# boson.net
KiCad netlist of a schematic drawn in EAGLE
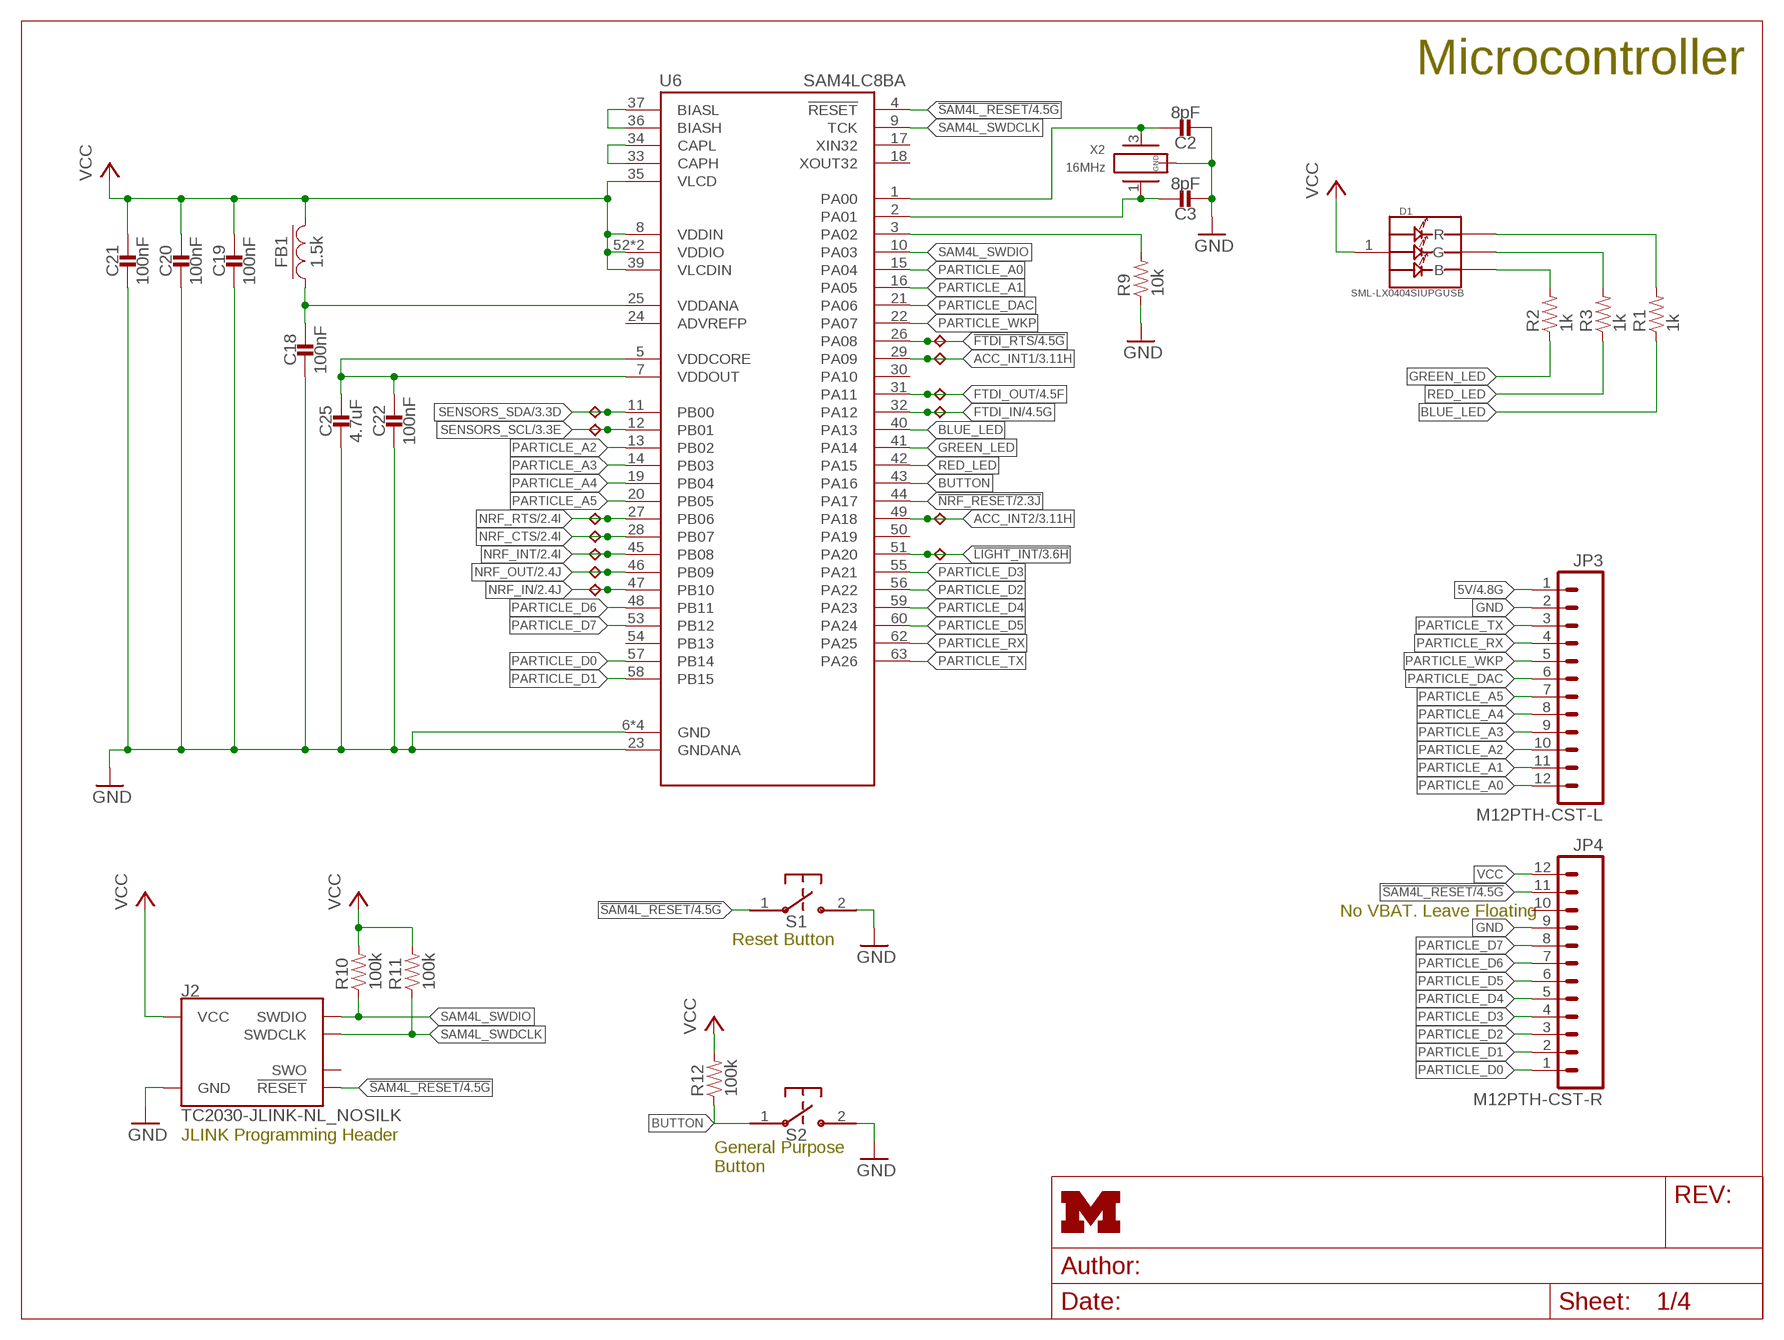
[diagram p0: schematic, sheet 1]
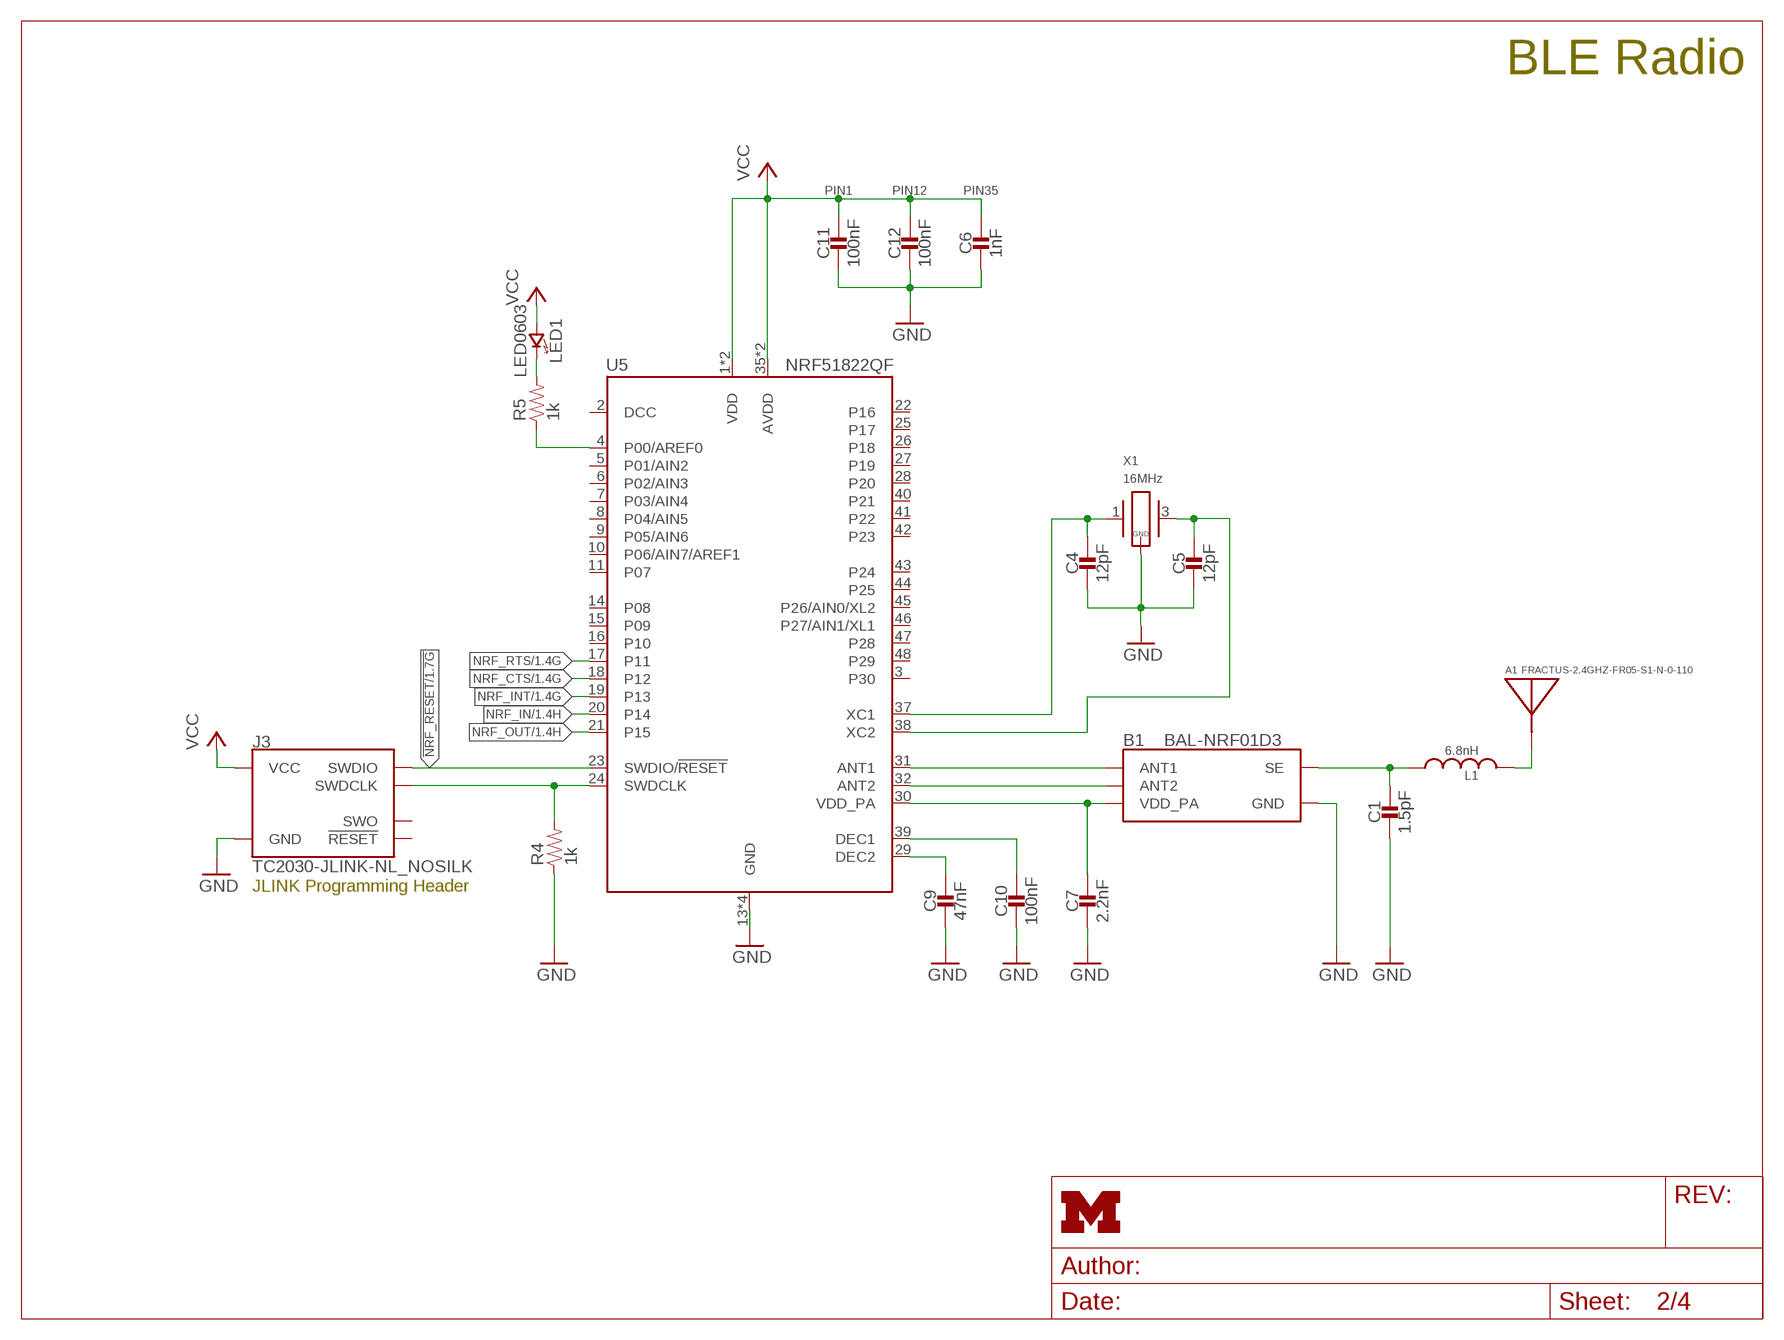
[diagram p1: schematic, sheet 2]
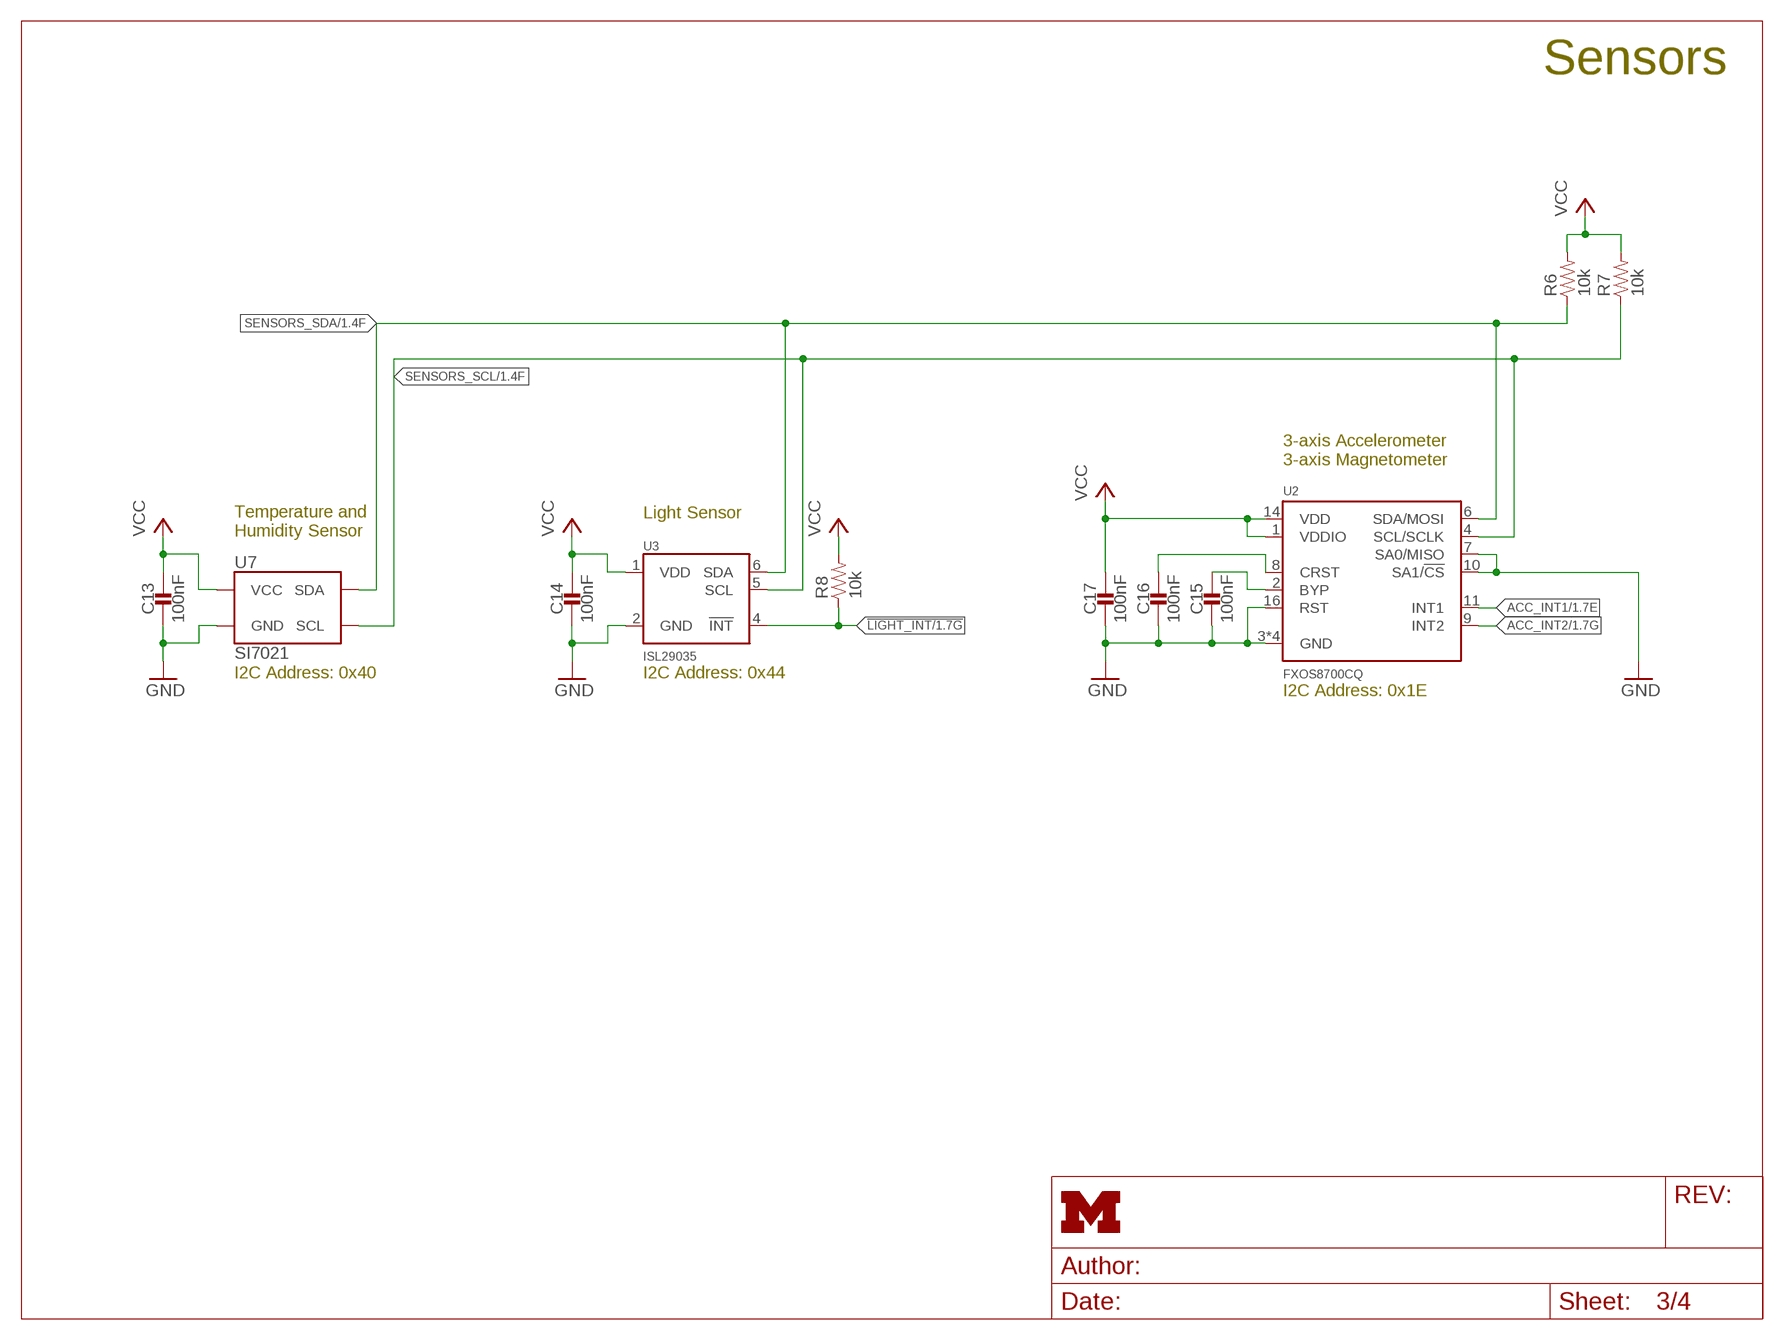
[diagram p2: schematic, sheet 3]
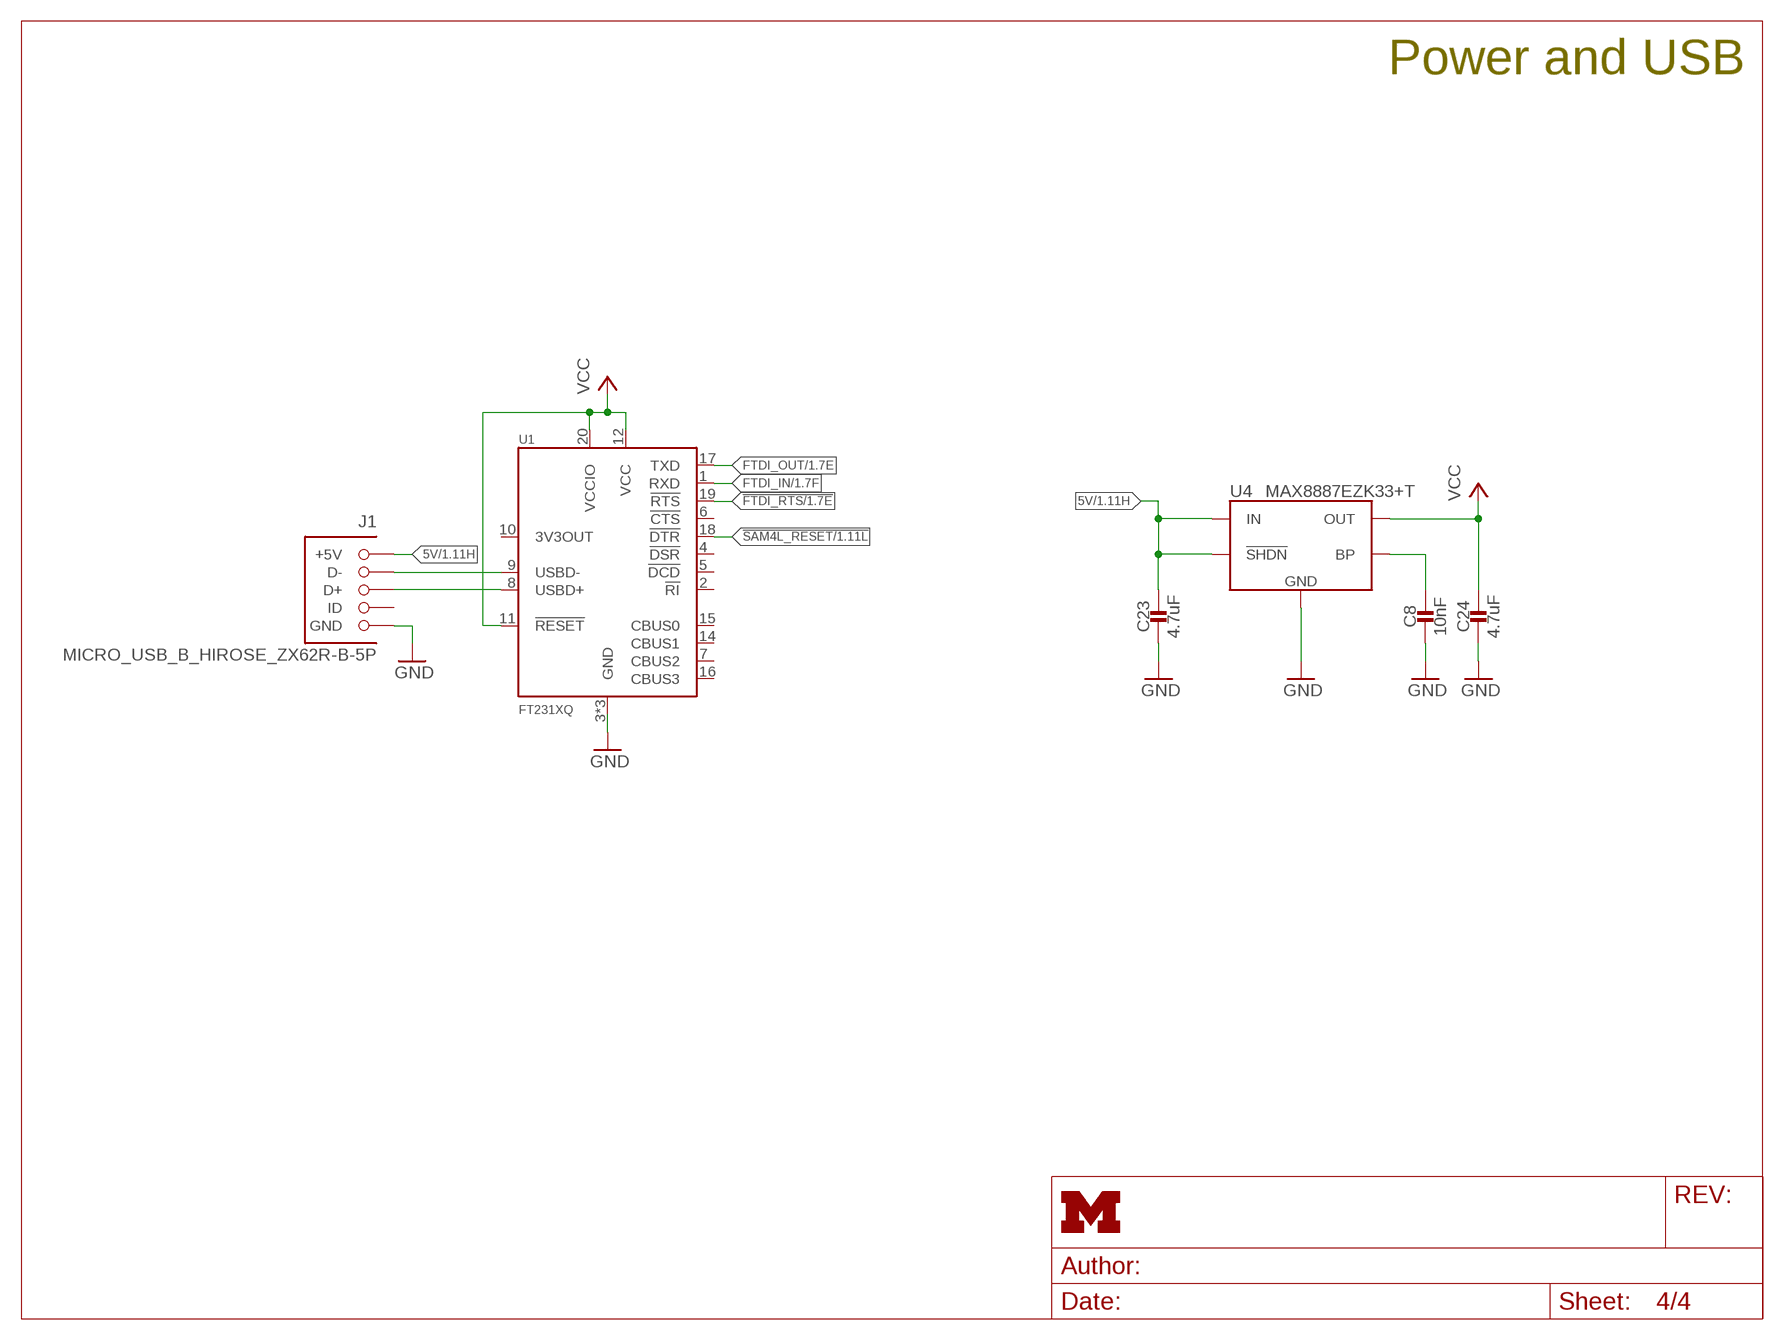
[diagram p3: schematic, sheet 4]

(export (version "E")
  (design (tool "Eeschema 10.0.6"))
  (components
    (comp (ref "C2")
      (value "8pF")
      (footprint "eagle-import:0402_CAP")
      (libsource (lib "eagle-import") (part "CAPACITOR0402_CAP"))
    )
    (comp (ref "C3")
      (value "8pF")
      (footprint "eagle-import:0402_CAP")
      (libsource (lib "eagle-import") (part "CAPACITOR0402_CAP"))
    )
    (comp (ref "C18")
      (value "100nF")
      (footprint "eagle-import:0402_CAP")
      (libsource (lib "eagle-import") (part "CAPACITOR0402_CAP"))
    )
    (comp (ref "C19")
      (value "100nF")
      (footprint "eagle-import:0402_CAP")
      (libsource (lib "eagle-import") (part "CAPACITOR0402_CAP"))
    )
    (comp (ref "C20")
      (value "100nF")
      (footprint "eagle-import:0402_CAP")
      (libsource (lib "eagle-import") (part "CAPACITOR0402_CAP"))
    )
    (comp (ref "C21")
      (value "100nF")
      (footprint "eagle-import:0402_CAP")
      (libsource (lib "eagle-import") (part "CAPACITOR0402_CAP"))
    )
    (comp (ref "C22")
      (value "100nF")
      (footprint "eagle-import:0402_CAP")
      (libsource (lib "eagle-import") (part "CAPACITOR0402_CAP"))
    )
    (comp (ref "C25")
      (value "4.7uF")
      (footprint "eagle-import:0402_CAP")
      (libsource (lib "eagle-import") (part "CAPACITOR0402_CAP"))
    )
    (comp (ref "D1")
      (value "SML-LX0404SIUPGUSB")
      (footprint "eagle-import:1MM_SQ_4PAD")
      (libsource (lib "eagle-import") (part "SML-LX0404SIUPGUSB"))
    )
    (comp (ref "FB1")
      (value "1.5k")
      (footprint "eagle-import:0402_CAP")
      (libsource (lib "eagle-import") (part "FERRITE_BEAD0402"))
    )
    (comp (ref "J2")
      (value "TC2030-JLINK-NL_NOSILK")
      (footprint "eagle-import:TC2030-IDC-NL_NOSILK")
      (libsource (lib "eagle-import") (part "TC2030-JLINK-NL_NOSILK"))
    )
    (comp (ref "JP3")
      (value "M12PTH-CST-L")
      (footprint "eagle-import:1X12-CASTELLATED")
      (libsource (lib "eagle-import") (part "M12PTH-CST-L"))
    )
    (comp (ref "JP4")
      (value "M12PTH-CST-R")
      (footprint "eagle-import:1X12-CASTELLATED")
      (libsource (lib "eagle-import") (part "M12PTH-CST-R"))
    )
    (comp (ref "R1")
      (value "1k")
      (footprint "eagle-import:0402_RES")
      (libsource (lib "eagle-import") (part "RESISTOR0402_RES"))
    )
    (comp (ref "R2")
      (value "1k")
      (footprint "eagle-import:0402_RES")
      (libsource (lib "eagle-import") (part "RESISTOR0402_RES"))
    )
    (comp (ref "R3")
      (value "1k")
      (footprint "eagle-import:0402_RES")
      (libsource (lib "eagle-import") (part "RESISTOR0402_RES"))
    )
    (comp (ref "R9")
      (value "10k")
      (footprint "eagle-import:0402_RES")
      (libsource (lib "eagle-import") (part "RESISTOR0402_RES"))
    )
    (comp (ref "R10")
      (value "100k")
      (footprint "eagle-import:0402_RES")
      (libsource (lib "eagle-import") (part "RESISTOR0402_RES"))
    )
    (comp (ref "R11")
      (value "100k")
      (footprint "eagle-import:0402_RES")
      (libsource (lib "eagle-import") (part "RESISTOR0402_RES"))
    )
    (comp (ref "R12")
      (value "100k")
      (footprint "eagle-import:0402_RES")
      (libsource (lib "eagle-import") (part "RESISTOR0402_RES"))
    )
    (comp (ref "S1")
      (value "B3U-1000P")
      (footprint "eagle-import:B3U-1000P")
      (libsource (lib "eagle-import") (part "B3U-1000P"))
    )
    (comp (ref "S2")
      (value "B3U-1000P")
      (footprint "eagle-import:B3U-1000P")
      (libsource (lib "eagle-import") (part "B3U-1000P"))
    )
    (comp (ref "TP1")
      (value "TPB1,27")
      (footprint "eagle-import:B1,27")
      (libsource (lib "eagle-import") (part "TPB1,27"))
    )
    (comp (ref "TP2")
      (value "TPB1,27")
      (footprint "eagle-import:B1,27")
      (libsource (lib "eagle-import") (part "TPB1,27"))
    )
    (comp (ref "TP3")
      (value "TPB1,27")
      (footprint "eagle-import:B1,27")
      (libsource (lib "eagle-import") (part "TPB1,27"))
    )
    (comp (ref "TP4")
      (value "TPB1,27")
      (footprint "eagle-import:B1,27")
      (libsource (lib "eagle-import") (part "TPB1,27"))
    )
    (comp (ref "TP5")
      (value "TPB1,27")
      (footprint "eagle-import:B1,27")
      (libsource (lib "eagle-import") (part "TPB1,27"))
    )
    (comp (ref "TP6")
      (value "TPB1,27")
      (footprint "eagle-import:B1,27")
      (libsource (lib "eagle-import") (part "TPB1,27"))
    )
    (comp (ref "TP7")
      (value "TPB1,27")
      (footprint "eagle-import:B1,27")
      (libsource (lib "eagle-import") (part "TPB1,27"))
    )
    (comp (ref "TP8")
      (value "TPB1,27")
      (footprint "eagle-import:B1,27")
      (libsource (lib "eagle-import") (part "TPB1,27"))
    )
    (comp (ref "TP9")
      (value "TPB1,27")
      (footprint "eagle-import:B1,27")
      (libsource (lib "eagle-import") (part "TPB1,27"))
    )
    (comp (ref "TP10")
      (value "TPB1,27")
      (footprint "eagle-import:B1,27")
      (libsource (lib "eagle-import") (part "TPB1,27"))
    )
    (comp (ref "TP11")
      (value "TPB1,27")
      (footprint "eagle-import:B1,27")
      (libsource (lib "eagle-import") (part "TPB1,27"))
    )
    (comp (ref "TP12")
      (value "TPB1,27")
      (footprint "eagle-import:B1,27")
      (libsource (lib "eagle-import") (part "TPB1,27"))
    )
    (comp (ref "TP13")
      (value "TPB1,27")
      (footprint "eagle-import:B1,27")
      (libsource (lib "eagle-import") (part "TPB1,27"))
    )
    (comp (ref "U6")
      (value "SAM4LC8BA")
      (footprint "eagle-import:QFN-64-9MM")
      (libsource (lib "eagle-import") (part "SAM4LC8BA"))
    )
    (comp (ref "X2")
      (value "16MHz")
      (footprint "eagle-import:FHXXX")
      (libsource (lib "eagle-import") (part "FH1600015"))
    )
    (comp (ref "C8")
      (value "10nF")
      (footprint "eagle-import:0402_CAP")
      (libsource (lib "eagle-import") (part "CAPACITOR0402_CAP"))
    )
    (comp (ref "C23")
      (value "4.7uF")
      (footprint "eagle-import:0402_CAP")
      (libsource (lib "eagle-import") (part "CAPACITOR0402_CAP"))
    )
    (comp (ref "C24")
      (value "4.7uF")
      (footprint "eagle-import:0402_CAP")
      (libsource (lib "eagle-import") (part "CAPACITOR0402_CAP"))
    )
    (comp (ref "J1")
      (value "MICRO_USB_B_HIROSE_ZX62R-B-5P")
      (footprint "eagle-import:USB_MICRO_B-HIROSE-ZX62R-B-5P")
      (fields (field (name "DIGIKEY") "H125274CT-ND"))
      (libsource (lib "eagle-import") (part "MICRO_USB_B_HIROSE_ZX62R-B-5P"))
    )
    (comp (ref "U1")
      (value "FT231XQ")
      (footprint "eagle-import:QFN-20-4MM")
      (fields (field (name "MPN") "FT231XQ-R"))
      (libsource (lib "eagle-import") (part "FT231XQ"))
    )
    (comp (ref "U4")
      (value "MAX8887EZK33+T")
      (footprint "eagle-import:SOT-23-5")
      (libsource (lib "eagle-import") (part "MAX8887EZK33+T"))
    )
    (comp (ref "C13")
      (value "100nF")
      (footprint "eagle-import:0402_CAP")
      (libsource (lib "eagle-import") (part "CAPACITOR0402_CAP"))
    )
    (comp (ref "C14")
      (value "100nF")
      (footprint "eagle-import:0402_CAP")
      (libsource (lib "eagle-import") (part "CAPACITOR0402_CAP"))
    )
    (comp (ref "C15")
      (value "100nF")
      (footprint "eagle-import:0402_CAP")
      (libsource (lib "eagle-import") (part "CAPACITOR0402_CAP"))
    )
    (comp (ref "C16")
      (value "100nF")
      (footprint "eagle-import:0402_CAP")
      (libsource (lib "eagle-import") (part "CAPACITOR0402_CAP"))
    )
    (comp (ref "C17")
      (value "100nF")
      (footprint "eagle-import:0402_CAP")
      (libsource (lib "eagle-import") (part "CAPACITOR0402_CAP"))
    )
    (comp (ref "R6")
      (value "10k")
      (footprint "eagle-import:0402_RES")
      (libsource (lib "eagle-import") (part "RESISTOR0402_RES"))
    )
    (comp (ref "R7")
      (value "10k")
      (footprint "eagle-import:0402_RES")
      (libsource (lib "eagle-import") (part "RESISTOR0402_RES"))
    )
    (comp (ref "R8")
      (value "10k")
      (footprint "eagle-import:0402_RES")
      (libsource (lib "eagle-import") (part "RESISTOR0402_RES"))
    )
    (comp (ref "U2")
      (value "FXOS8700CQ")
      (footprint "eagle-import:QFN-16-3MM")
      (fields (field (name "MPN") "FXOS8700CQR1"))
      (libsource (lib "eagle-import") (part "FXOS8700CQ"))
    )
    (comp (ref "U3")
      (value "ISL29035")
      (footprint "eagle-import:ODFN-6-1.5MMX1.6MM")
      (fields (field (name "MPN") "ISL29035IROZ-T7"))
      (libsource (lib "eagle-import") (part "ISL29035"))
    )
    (comp (ref "U7")
      (value "SI7021")
      (footprint "eagle-import:DFN-6_3MM")
      (libsource (lib "eagle-import") (part "SI7021"))
    )
    (comp (ref "A1")
      (value "FRACTUS-2.4GHZ-FR05-S1-N-0-110")
      (footprint "eagle-import:FRACTUS-ANTENNA-FR05-S1-N-0-110")
      (libsource (lib "eagle-import") (part "FRACTUS-2.4GHZ-FR05-S1-N-0-110"))
    )
    (comp (ref "B1")
      (value "BAL-NRF01D3")
      (footprint "eagle-import:BAL-NRF01D3")
      (libsource (lib "eagle-import") (part "BAL-NRF01D3"))
    )
    (comp (ref "C1")
      (value "1.5pF")
      (footprint "eagle-import:0402_CAP")
      (libsource (lib "eagle-import") (part "CAPACITOR0402_CAP"))
    )
    (comp (ref "C4")
      (value "12pF")
      (footprint "eagle-import:0402_CAP")
      (libsource (lib "eagle-import") (part "CAPACITOR0402_CAP"))
    )
    (comp (ref "C5")
      (value "12pF")
      (footprint "eagle-import:0402_CAP")
      (libsource (lib "eagle-import") (part "CAPACITOR0402_CAP"))
    )
    (comp (ref "C6")
      (value "1nF")
      (footprint "eagle-import:0402_CAP")
      (libsource (lib "eagle-import") (part "CAPACITOR0402_CAP"))
    )
    (comp (ref "C7")
      (value "2.2nF")
      (footprint "eagle-import:0402_CAP")
      (libsource (lib "eagle-import") (part "CAPACITOR0402_CAP"))
    )
    (comp (ref "C9")
      (value "47nF")
      (footprint "eagle-import:0402_CAP")
      (libsource (lib "eagle-import") (part "CAPACITOR0402_CAP"))
    )
    (comp (ref "C10")
      (value "100nF")
      (footprint "eagle-import:0402_CAP")
      (libsource (lib "eagle-import") (part "CAPACITOR0402_CAP"))
    )
    (comp (ref "C11")
      (value "100nF")
      (footprint "eagle-import:0402_CAP")
      (libsource (lib "eagle-import") (part "CAPACITOR0402_CAP"))
    )
    (comp (ref "C12")
      (value "100nF")
      (footprint "eagle-import:0402_CAP")
      (libsource (lib "eagle-import") (part "CAPACITOR0402_CAP"))
    )
    (comp (ref "J3")
      (value "TC2030-JLINK-NL_NOSILK")
      (footprint "eagle-import:TC2030-IDC-NL_NOSILK")
      (libsource (lib "eagle-import") (part "TC2030-JLINK-NL_NOSILK"))
    )
    (comp (ref "L1")
      (value "6.8nH")
      (footprint "eagle-import:0402_CAP")
      (libsource (lib "eagle-import") (part "INDUCTOR0402"))
    )
    (comp (ref "LED1")
      (value "LED0603")
      (footprint "eagle-import:LED-0603")
      (libsource (lib "eagle-import") (part "LED0603"))
    )
    (comp (ref "R4")
      (value "1k")
      (footprint "eagle-import:0402_RES")
      (libsource (lib "eagle-import") (part "RESISTOR0402_RES"))
    )
    (comp (ref "R5")
      (value "1k")
      (footprint "eagle-import:0402_RES")
      (libsource (lib "eagle-import") (part "RESISTOR0402_RES"))
    )
    (comp (ref "U5")
      (value "NRF51822QF")
      (footprint "eagle-import:QFN-48-6MM")
      (libsource (lib "eagle-import") (part "NRF51822QF"))
    )
    (comp (ref "X1")
      (value "16MHz")
      (footprint "eagle-import:TXC-8Y")
      (libsource (lib "eagle-import") (part "TXC-8Y"))
    )
  )
  (nets
    (net (code "1") (name "5V") (class "Default")
      (node (ref "C23") (pin "1") (pinfunction "1_1") (pintype "bidirectional"))
      (node (ref "J1") (pin "1") (pinfunction "+5V_1") (pintype "bidirectional"))
      (node (ref "JP3") (pin "1") (pinfunction "12_1") (pintype "passive"))
      (node (ref "U4") (pin "1") (pinfunction "IN_1") (pintype "bidirectional"))
      (node (ref "U4") (pin "3") (pinfunction "~{SHDN}_3") (pintype "bidirectional"))
    )
    (net (code "2") (name "ACC_INT1") (class "Default")
      (node (ref "TP8") (pin "TP") (pinfunction "TP_TP") (pintype "input"))
      (node (ref "U2") (pin "11") (pinfunction "INT1_11") (pintype "bidirectional"))
      (node (ref "U6") (pin "29") (pinfunction "PA09_29") (pintype "bidirectional"))
    )
    (net (code "3") (name "ACC_INT2") (class "Default")
      (node (ref "TP9") (pin "TP") (pinfunction "TP_TP") (pintype "input"))
      (node (ref "U2") (pin "9") (pinfunction "INT2_9") (pintype "bidirectional"))
      (node (ref "U6") (pin "49") (pinfunction "PA18_49") (pintype "bidirectional"))
    )
    (net (code "4") (name "ADVREFP") (class "Default")
      (node (ref "U6") (pin "24") (pinfunction "ADVREFP_24") (pintype "power_in"))
    )
    (net (code "5") (name "BLUE_LED") (class "Default")
      (node (ref "R1") (pin "1") (pinfunction "1_1") (pintype "passive"))
      (node (ref "U6") (pin "40") (pinfunction "PA13_40") (pintype "bidirectional"))
    )
    (net (code "6") (name "BUTTON") (class "Default")
      (node (ref "R12") (pin "1") (pinfunction "1_1") (pintype "passive"))
      (node (ref "S2") (pin "1") (pinfunction "P$1_1") (pintype "passive"))
      (node (ref "U6") (pin "43") (pinfunction "PA16_43") (pintype "bidirectional"))
    )
    (net (code "7") (name "FTDI_IN") (class "Default")
      (node (ref "TP13") (pin "TP") (pinfunction "TP_TP") (pintype "input"))
      (node (ref "U1") (pin "1") (pinfunction "RXD_1") (pintype "bidirectional"))
      (node (ref "U6") (pin "32") (pinfunction "PA12_32") (pintype "bidirectional"))
    )
    (net (code "8") (name "FTDI_OUT") (class "Default")
      (node (ref "TP12") (pin "TP") (pinfunction "TP_TP") (pintype "input"))
      (node (ref "U1") (pin "17") (pinfunction "TXD_17") (pintype "bidirectional"))
      (node (ref "U6") (pin "31") (pinfunction "PA11_31") (pintype "bidirectional"))
    )
    (net (code "9") (name "GND") (class "Default")
      (node (ref "B1") (pin "GND") (pinfunction "GND_GND") (pintype "bidirectional"))
      (node (ref "C1") (pin "2") (pinfunction "2_2") (pintype "bidirectional"))
      (node (ref "C10") (pin "2") (pinfunction "2_2") (pintype "bidirectional"))
      (node (ref "C11") (pin "2") (pinfunction "2_2") (pintype "bidirectional"))
      (node (ref "C12") (pin "2") (pinfunction "2_2") (pintype "bidirectional"))
      (node (ref "C13") (pin "2") (pinfunction "2_2") (pintype "bidirectional"))
      (node (ref "C14") (pin "2") (pinfunction "2_2") (pintype "bidirectional"))
      (node (ref "C15") (pin "2") (pinfunction "2_2") (pintype "bidirectional"))
      (node (ref "C16") (pin "2") (pinfunction "2_2") (pintype "bidirectional"))
      (node (ref "C17") (pin "2") (pinfunction "2_2") (pintype "bidirectional"))
      (node (ref "C18") (pin "2") (pinfunction "2_2") (pintype "bidirectional"))
      (node (ref "C19") (pin "2") (pinfunction "2_2") (pintype "bidirectional"))
      (node (ref "C2") (pin "2") (pinfunction "2_2") (pintype "bidirectional"))
      (node (ref "C20") (pin "2") (pinfunction "2_2") (pintype "bidirectional"))
      (node (ref "C21") (pin "2") (pinfunction "2_2") (pintype "bidirectional"))
      (node (ref "C22") (pin "2") (pinfunction "2_2") (pintype "bidirectional"))
      (node (ref "C23") (pin "2") (pinfunction "2_2") (pintype "bidirectional"))
      (node (ref "C24") (pin "2") (pinfunction "2_2") (pintype "bidirectional"))
      (node (ref "C25") (pin "2") (pinfunction "2_2") (pintype "bidirectional"))
      (node (ref "C3") (pin "2") (pinfunction "2_2") (pintype "bidirectional"))
      (node (ref "C4") (pin "2") (pinfunction "2_2") (pintype "bidirectional"))
      (node (ref "C5") (pin "2") (pinfunction "2_2") (pintype "bidirectional"))
      (node (ref "C6") (pin "2") (pinfunction "2_2") (pintype "bidirectional"))
      (node (ref "C7") (pin "2") (pinfunction "2_2") (pintype "bidirectional"))
      (node (ref "C8") (pin "2") (pinfunction "2_2") (pintype "bidirectional"))
      (node (ref "C9") (pin "2") (pinfunction "2_2") (pintype "bidirectional"))
      (node (ref "J1") (pin "5") (pinfunction "GND_5") (pintype "bidirectional"))
      (node (ref "J2") (pin "5") (pinfunction "GND_5") (pintype "bidirectional"))
      (node (ref "J3") (pin "5") (pinfunction "GND_5") (pintype "bidirectional"))
      (node (ref "JP3") (pin "2") (pinfunction "11_2") (pintype "passive"))
      (node (ref "JP4") (pin "9") (pinfunction "9_9") (pintype "passive"))
      (node (ref "R4") (pin "1") (pinfunction "1_1") (pintype "passive"))
      (node (ref "R9") (pin "1") (pinfunction "1_1") (pintype "passive"))
      (node (ref "S1") (pin "2") (pinfunction "P$2_2") (pintype "passive"))
      (node (ref "S2") (pin "2") (pinfunction "P$2_2") (pintype "passive"))
      (node (ref "U1") (pin "13") (pinfunction "GND_13") (pintype "bidirectional"))
      (node (ref "U1") (pin "3") (pinfunction "GND_3") (pintype "bidirectional"))
      (node (ref "U1") (pin "GND") (pinfunction "GND_GND") (pintype "bidirectional"))
      (node (ref "U2") (pin "10") (pinfunction "SA1/~{CS}_10") (pintype "bidirectional"))
      (node (ref "U2") (pin "12") (pinfunction "GND_12") (pintype "bidirectional"))
      (node (ref "U2") (pin "13") (pinfunction "GND_13") (pintype "bidirectional"))
      (node (ref "U2") (pin "16") (pinfunction "RST_16") (pintype "bidirectional"))
      (node (ref "U2") (pin "3") (pinfunction "GND_3") (pintype "bidirectional"))
      (node (ref "U2") (pin "5") (pinfunction "GND_5") (pintype "bidirectional"))
      (node (ref "U2") (pin "7") (pinfunction "SA0/MISO_7") (pintype "bidirectional"))
      (node (ref "U3") (pin "2") (pinfunction "GND_2") (pintype "bidirectional"))
      (node (ref "U4") (pin "2") (pinfunction "GND_2") (pintype "bidirectional"))
      (node (ref "U5") (pin "13") (pinfunction "GND_13") (pintype "bidirectional"))
      (node (ref "U5") (pin "33") (pinfunction "GND_33") (pintype "bidirectional"))
      (node (ref "U5") (pin "34") (pinfunction "GND_34") (pintype "bidirectional"))
      (node (ref "U5") (pin "GND") (pinfunction "GND_GND") (pintype "bidirectional"))
      (node (ref "U6") (pin "23") (pinfunction "GNDANA_23") (pintype "power_in"))
      (node (ref "U6") (pin "38") (pinfunction "GND_38") (pintype "power_in"))
      (node (ref "U6") (pin "6") (pinfunction "GND_6") (pintype "power_in"))
      (node (ref "U6") (pin "64") (pinfunction "GND_64") (pintype "power_in"))
      (node (ref "U6") (pin "GND") (pinfunction "GND_GND") (pintype "power_in"))
      (node (ref "U7") (pin "2") (pinfunction "GND_2") (pintype "bidirectional"))
      (node (ref "X1") (pin "2") (pinfunction "GND_2") (pintype "bidirectional"))
      (node (ref "X1") (pin "4") (pinfunction "GND_4") (pintype "bidirectional"))
      (node (ref "X2") (pin "2") (pinfunction "GND_2") (pintype "bidirectional"))
      (node (ref "X2") (pin "4") (pinfunction "GND_4") (pintype "bidirectional"))
    )
    (net (code "10") (name "GREEN_LED") (class "Default")
      (node (ref "R2") (pin "1") (pinfunction "1_1") (pintype "passive"))
      (node (ref "U6") (pin "41") (pinfunction "PA14_41") (pintype "bidirectional"))
    )
    (net (code "11") (name "NRF_CTS") (class "Default")
      (node (ref "TP2") (pin "TP") (pinfunction "TP_TP") (pintype "input"))
      (node (ref "U5") (pin "18") (pinfunction "P12_18") (pintype "bidirectional"))
      (node (ref "U6") (pin "28") (pinfunction "PB07_28") (pintype "bidirectional"))
    )
    (net (code "12") (name "NRF_IN") (class "Default")
      (node (ref "TP5") (pin "TP") (pinfunction "TP_TP") (pintype "input"))
      (node (ref "U5") (pin "20") (pinfunction "P14_20") (pintype "bidirectional"))
      (node (ref "U6") (pin "47") (pinfunction "PB10_47") (pintype "bidirectional"))
    )
    (net (code "13") (name "NRF_INT") (class "Default")
      (node (ref "TP3") (pin "TP") (pinfunction "TP_TP") (pintype "input"))
      (node (ref "U5") (pin "19") (pinfunction "P13_19") (pintype "bidirectional"))
      (node (ref "U6") (pin "45") (pinfunction "PB08_45") (pintype "bidirectional"))
    )
    (net (code "14") (name "NRF_OUT") (class "Default")
      (node (ref "TP4") (pin "TP") (pinfunction "TP_TP") (pintype "input"))
      (node (ref "U5") (pin "21") (pinfunction "P15_21") (pintype "bidirectional"))
      (node (ref "U6") (pin "46") (pinfunction "PB09_46") (pintype "bidirectional"))
    )
    (net (code "15") (name "NRF_RTS") (class "Default")
      (node (ref "TP1") (pin "TP") (pinfunction "TP_TP") (pintype "input"))
      (node (ref "U5") (pin "17") (pinfunction "P11_17") (pintype "bidirectional"))
      (node (ref "U6") (pin "27") (pinfunction "PB06_27") (pintype "bidirectional"))
    )
    (net (code "16") (name "Net-(A1-ANTENNA)") (class "Default")
      (node (ref "A1") (pin "ANT") (pinfunction "ANTENNA_ANT") (pintype "bidirectional"))
      (node (ref "L1") (pin "2") (pinfunction "2_2") (pintype "bidirectional"))
    )
    (net (code "17") (name "Net-(B1-PadSE)") (class "Default")
      (node (ref "B1") (pin "SE") (pinfunction "SE_SE") (pintype "bidirectional"))
      (node (ref "C1") (pin "1") (pinfunction "1_1") (pintype "bidirectional"))
      (node (ref "L1") (pin "1") (pinfunction "1_1") (pintype "bidirectional"))
    )
    (net (code "18") (name "Net-(B1-VDD_PA)") (class "Default")
      (node (ref "B1") (pin "VCC") (pinfunction "VDD_PA_VCC") (pintype "bidirectional"))
      (node (ref "C7") (pin "1") (pinfunction "1_1") (pintype "bidirectional"))
      (node (ref "U5") (pin "30") (pinfunction "VDD_PA_30") (pintype "bidirectional"))
    )
    (net (code "19") (name "Net-(D1-B)") (class "Default")
      (node (ref "D1") (pin "3") (pinfunction "B_3") (pintype "output"))
      (node (ref "R2") (pin "2") (pinfunction "2_2") (pintype "passive"))
    )
    (net (code "20") (name "Net-(D1-G)") (class "Default")
      (node (ref "D1") (pin "4") (pinfunction "G_4") (pintype "output"))
      (node (ref "R3") (pin "2") (pinfunction "2_2") (pintype "passive"))
    )
    (net (code "21") (name "Net-(D1-R)") (class "Default")
      (node (ref "D1") (pin "2") (pinfunction "R_2") (pintype "output"))
      (node (ref "R1") (pin "2") (pinfunction "2_2") (pintype "passive"))
    )
    (net (code "22") (name "Net-(FB1-P$1)") (class "Default")
      (node (ref "C18") (pin "1") (pinfunction "1_1") (pintype "bidirectional"))
      (node (ref "FB1") (pin "1") (pinfunction "P$1_1") (pintype "bidirectional"))
      (node (ref "U6") (pin "25") (pinfunction "VDDANA_25") (pintype "power_in"))
    )
    (net (code "23") (name "Net-(J1-D+)") (class "Default")
      (node (ref "J1") (pin "3") (pinfunction "D+_3") (pintype "bidirectional"))
      (node (ref "U1") (pin "8") (pinfunction "USBD+_8") (pintype "bidirectional"))
    )
    (net (code "24") (name "Net-(J1-D-)") (class "Default")
      (node (ref "J1") (pin "2") (pinfunction "D-_2") (pintype "bidirectional"))
      (node (ref "U1") (pin "9") (pinfunction "USBD-_9") (pintype "bidirectional"))
    )
    (net (code "25") (name "Net-(J3-SWDCLK)") (class "Default")
      (node (ref "J3") (pin "4") (pinfunction "SWDCLK_4") (pintype "bidirectional"))
      (node (ref "R4") (pin "2") (pinfunction "2_2") (pintype "passive"))
      (node (ref "U5") (pin "24") (pinfunction "SWDCLK_24") (pintype "bidirectional"))
    )
    (net (code "26") (name "Net-(LED1-CATHODE)") (class "Default")
      (node (ref "LED1") (pin "C") (pinfunction "CATHODE_C") (pintype "bidirectional"))
      (node (ref "R5") (pin "2") (pinfunction "2_2") (pintype "passive"))
    )
    (net (code "27") (name "Net-(U2-BYP)") (class "Default")
      (node (ref "C15") (pin "1") (pinfunction "1_1") (pintype "bidirectional"))
      (node (ref "U2") (pin "2") (pinfunction "BYP_2") (pintype "bidirectional"))
    )
    (net (code "28") (name "Net-(U2-CRST)") (class "Default")
      (node (ref "C16") (pin "1") (pinfunction "1_1") (pintype "bidirectional"))
      (node (ref "U2") (pin "8") (pinfunction "CRST_8") (pintype "bidirectional"))
    )
    (net (code "29") (name "Net-(U4-BP)") (class "Default")
      (node (ref "C8") (pin "1") (pinfunction "1_1") (pintype "bidirectional"))
      (node (ref "U4") (pin "4") (pinfunction "BP_4") (pintype "bidirectional"))
    )
    (net (code "30") (name "Net-(U5-ANT1)") (class "Default")
      (node (ref "B1") (pin "ANT1") (pinfunction "ANT1_ANT1") (pintype "bidirectional"))
      (node (ref "U5") (pin "31") (pinfunction "ANT1_31") (pintype "bidirectional"))
    )
    (net (code "31") (name "Net-(U5-ANT2)") (class "Default")
      (node (ref "B1") (pin "ANT2") (pinfunction "ANT2_ANT2") (pintype "bidirectional"))
      (node (ref "U5") (pin "32") (pinfunction "ANT2_32") (pintype "bidirectional"))
    )
    (net (code "32") (name "Net-(U5-DEC1)") (class "Default")
      (node (ref "C10") (pin "1") (pinfunction "1_1") (pintype "bidirectional"))
      (node (ref "U5") (pin "39") (pinfunction "DEC1_39") (pintype "bidirectional"))
    )
    (net (code "33") (name "Net-(U5-DEC2)") (class "Default")
      (node (ref "C9") (pin "1") (pinfunction "1_1") (pintype "bidirectional"))
      (node (ref "U5") (pin "29") (pinfunction "DEC2_29") (pintype "bidirectional"))
    )
    (net (code "34") (name "Net-(U5-P00{slash}AREF0)") (class "Default")
      (node (ref "R5") (pin "1") (pinfunction "1_1") (pintype "passive"))
      (node (ref "U5") (pin "4") (pinfunction "P00/AREF0_4") (pintype "bidirectional"))
    )
    (net (code "35") (name "Net-(U5-XC1)") (class "Default")
      (node (ref "C4") (pin "1") (pinfunction "1_1") (pintype "bidirectional"))
      (node (ref "U5") (pin "37") (pinfunction "XC1_37") (pintype "bidirectional"))
      (node (ref "X1") (pin "1") (pinfunction "1_1") (pintype "bidirectional"))
    )
    (net (code "36") (name "Net-(U5-XC2)") (class "Default")
      (node (ref "C5") (pin "1") (pinfunction "1_1") (pintype "bidirectional"))
      (node (ref "U5") (pin "38") (pinfunction "XC2_38") (pintype "bidirectional"))
      (node (ref "X1") (pin "3") (pinfunction "2_3") (pintype "bidirectional"))
    )
    (net (code "37") (name "Net-(U6-BIASH)") (class "Default")
      (node (ref "U6") (pin "36") (pinfunction "BIASH_36") (pintype "bidirectional"))
      (node (ref "U6") (pin "37") (pinfunction "BIASL_37") (pintype "bidirectional"))
    )
    (net (code "38") (name "Net-(U6-CAPH)") (class "Default")
      (node (ref "U6") (pin "33") (pinfunction "CAPH_33") (pintype "bidirectional"))
      (node (ref "U6") (pin "34") (pinfunction "CAPL_34") (pintype "bidirectional"))
    )
    (net (code "39") (name "Net-(U6-PA00)") (class "Default")
      (node (ref "C2") (pin "1") (pinfunction "1_1") (pintype "bidirectional"))
      (node (ref "U6") (pin "1") (pinfunction "PA00_1") (pintype "bidirectional"))
      (node (ref "X2") (pin "3") (pinfunction "2_3") (pintype "bidirectional"))
    )
    (net (code "40") (name "Net-(U6-PA01)") (class "Default")
      (node (ref "C3") (pin "1") (pinfunction "1_1") (pintype "bidirectional"))
      (node (ref "U6") (pin "2") (pinfunction "PA01_2") (pintype "bidirectional"))
      (node (ref "X2") (pin "1") (pinfunction "1_1") (pintype "bidirectional"))
    )
    (net (code "41") (name "Net-(U6-PA02)") (class "Default")
      (node (ref "R9") (pin "2") (pinfunction "2_2") (pintype "passive"))
      (node (ref "U6") (pin "3") (pinfunction "PA02_3") (pintype "bidirectional"))
    )
    (net (code "42") (name "Net-(U6-VDDCORE)") (class "Default")
      (node (ref "C22") (pin "1") (pinfunction "1_1") (pintype "bidirectional"))
      (node (ref "C25") (pin "1") (pinfunction "1_1") (pintype "bidirectional"))
      (node (ref "U6") (pin "5") (pinfunction "VDDCORE_5") (pintype "power_in"))
      (node (ref "U6") (pin "7") (pinfunction "VDDOUT_7") (pintype "power_in"))
    )
    (net (code "43") (name "PARTICLE_A0") (class "Default")
      (node (ref "JP3") (pin "12") (pinfunction "1_12") (pintype "passive"))
      (node (ref "U6") (pin "15") (pinfunction "PA04_15") (pintype "bidirectional"))
    )
    (net (code "44") (name "PARTICLE_A1") (class "Default")
      (node (ref "JP3") (pin "11") (pinfunction "2_11") (pintype "passive"))
      (node (ref "U6") (pin "16") (pinfunction "PA05_16") (pintype "bidirectional"))
    )
    (net (code "45") (name "PARTICLE_A2") (class "Default")
      (node (ref "JP3") (pin "10") (pinfunction "3_10") (pintype "passive"))
      (node (ref "U6") (pin "13") (pinfunction "PB02_13") (pintype "bidirectional"))
    )
    (net (code "46") (name "PARTICLE_A3") (class "Default")
      (node (ref "JP3") (pin "9") (pinfunction "4_9") (pintype "passive"))
      (node (ref "U6") (pin "14") (pinfunction "PB03_14") (pintype "bidirectional"))
    )
    (net (code "47") (name "PARTICLE_A4") (class "Default")
      (node (ref "JP3") (pin "8") (pinfunction "5_8") (pintype "passive"))
      (node (ref "U6") (pin "19") (pinfunction "PB04_19") (pintype "bidirectional"))
    )
    (net (code "48") (name "PARTICLE_A5") (class "Default")
      (node (ref "JP3") (pin "7") (pinfunction "6_7") (pintype "passive"))
      (node (ref "U6") (pin "20") (pinfunction "PB05_20") (pintype "bidirectional"))
    )
    (net (code "49") (name "PARTICLE_D0") (class "Default")
      (node (ref "JP4") (pin "1") (pinfunction "1_1") (pintype "passive"))
      (node (ref "U6") (pin "57") (pinfunction "PB14_57") (pintype "bidirectional"))
    )
    (net (code "50") (name "PARTICLE_D1") (class "Default")
      (node (ref "JP4") (pin "2") (pinfunction "2_2") (pintype "passive"))
      (node (ref "U6") (pin "58") (pinfunction "PB15_58") (pintype "bidirectional"))
    )
    (net (code "51") (name "PARTICLE_D2") (class "Default")
      (node (ref "JP4") (pin "3") (pinfunction "3_3") (pintype "passive"))
      (node (ref "U6") (pin "56") (pinfunction "PA22_56") (pintype "bidirectional"))
    )
    (net (code "52") (name "PARTICLE_D3") (class "Default")
      (node (ref "JP4") (pin "4") (pinfunction "4_4") (pintype "passive"))
      (node (ref "U6") (pin "55") (pinfunction "PA21_55") (pintype "bidirectional"))
    )
    (net (code "53") (name "PARTICLE_D4") (class "Default")
      (node (ref "JP4") (pin "5") (pinfunction "5_5") (pintype "passive"))
      (node (ref "U6") (pin "59") (pinfunction "PA23_59") (pintype "bidirectional"))
    )
    (net (code "54") (name "PARTICLE_D5") (class "Default")
      (node (ref "JP4") (pin "6") (pinfunction "6_6") (pintype "passive"))
      (node (ref "U6") (pin "60") (pinfunction "PA24_60") (pintype "bidirectional"))
    )
    (net (code "55") (name "PARTICLE_D6") (class "Default")
      (node (ref "JP4") (pin "7") (pinfunction "7_7") (pintype "passive"))
      (node (ref "U6") (pin "48") (pinfunction "PB11_48") (pintype "bidirectional"))
    )
    (net (code "56") (name "PARTICLE_D7") (class "Default")
      (node (ref "JP4") (pin "8") (pinfunction "8_8") (pintype "passive"))
      (node (ref "U6") (pin "53") (pinfunction "PB12_53") (pintype "bidirectional"))
    )
    (net (code "57") (name "PARTICLE_DAC") (class "Default")
      (node (ref "JP3") (pin "6") (pinfunction "7_6") (pintype "passive"))
      (node (ref "U6") (pin "21") (pinfunction "PA06_21") (pintype "bidirectional"))
    )
    (net (code "58") (name "PARTICLE_RX") (class "Default")
      (node (ref "JP3") (pin "4") (pinfunction "9_4") (pintype "passive"))
      (node (ref "U6") (pin "62") (pinfunction "PA25_62") (pintype "bidirectional"))
    )
    (net (code "59") (name "PARTICLE_TX") (class "Default")
      (node (ref "JP3") (pin "3") (pinfunction "10_3") (pintype "passive"))
      (node (ref "U6") (pin "63") (pinfunction "PA26_63") (pintype "bidirectional"))
    )
    (net (code "60") (name "PARTICLE_WKP") (class "Default")
      (node (ref "JP3") (pin "5") (pinfunction "8_5") (pintype "passive"))
      (node (ref "U6") (pin "22") (pinfunction "PA07_22") (pintype "bidirectional"))
    )
    (net (code "61") (name "RED_LED") (class "Default")
      (node (ref "R3") (pin "1") (pinfunction "1_1") (pintype "passive"))
      (node (ref "U6") (pin "42") (pinfunction "PA15_42") (pintype "bidirectional"))
    )
    (net (code "62") (name "SAM4L_SWDCLK") (class "Default")
      (node (ref "J2") (pin "4") (pinfunction "SWDCLK_4") (pintype "bidirectional"))
      (node (ref "R11") (pin "1") (pinfunction "1_1") (pintype "passive"))
      (node (ref "U6") (pin "9") (pinfunction "TCK_9") (pintype "bidirectional"))
    )
    (net (code "63") (name "SAM4L_SWDIO") (class "Default")
      (node (ref "J2") (pin "2") (pinfunction "SWDIO_2") (pintype "bidirectional"))
      (node (ref "R10") (pin "1") (pinfunction "1_1") (pintype "passive"))
      (node (ref "U6") (pin "10") (pinfunction "PA03_10") (pintype "bidirectional"))
    )
    (net (code "64") (name "SENSORS_SCL") (class "Default")
      (node (ref "R7") (pin "1") (pinfunction "1_1") (pintype "passive"))
      (node (ref "TP7") (pin "TP") (pinfunction "TP_TP") (pintype "input"))
      (node (ref "U2") (pin "4") (pinfunction "SCL/SCLK_4") (pintype "bidirectional"))
      (node (ref "U3") (pin "5") (pinfunction "SCL_5") (pintype "bidirectional"))
      (node (ref "U6") (pin "12") (pinfunction "PB01_12") (pintype "bidirectional"))
      (node (ref "U7") (pin "6") (pinfunction "SCL_6") (pintype "bidirectional"))
    )
    (net (code "65") (name "SENSORS_SDA") (class "Default")
      (node (ref "R6") (pin "1") (pinfunction "1_1") (pintype "passive"))
      (node (ref "TP6") (pin "TP") (pinfunction "TP_TP") (pintype "input"))
      (node (ref "U2") (pin "6") (pinfunction "SDA/MOSI_6") (pintype "bidirectional"))
      (node (ref "U3") (pin "6") (pinfunction "SDA_6") (pintype "bidirectional"))
      (node (ref "U6") (pin "11") (pinfunction "PB00_11") (pintype "bidirectional"))
      (node (ref "U7") (pin "1") (pinfunction "SDA_1") (pintype "bidirectional"))
    )
    (net (code "66") (name "VCC") (class "Default")
      (node (ref "C11") (pin "1") (pinfunction "1_1") (pintype "bidirectional"))
      (node (ref "C12") (pin "1") (pinfunction "1_1") (pintype "bidirectional"))
      (node (ref "C13") (pin "1") (pinfunction "1_1") (pintype "bidirectional"))
      (node (ref "C14") (pin "1") (pinfunction "1_1") (pintype "bidirectional"))
      (node (ref "C17") (pin "1") (pinfunction "1_1") (pintype "bidirectional"))
      (node (ref "C19") (pin "1") (pinfunction "1_1") (pintype "bidirectional"))
      (node (ref "C20") (pin "1") (pinfunction "1_1") (pintype "bidirectional"))
      (node (ref "C21") (pin "1") (pinfunction "1_1") (pintype "bidirectional"))
      (node (ref "C24") (pin "1") (pinfunction "1_1") (pintype "bidirectional"))
      (node (ref "C6") (pin "1") (pinfunction "1_1") (pintype "bidirectional"))
      (node (ref "D1") (pin "1") (pinfunction "VDD_1") (pintype "bidirectional"))
      (node (ref "FB1") (pin "2") (pinfunction "P$2_2") (pintype "bidirectional"))
      (node (ref "J2") (pin "1") (pinfunction "VCC_1") (pintype "bidirectional"))
      (node (ref "J3") (pin "1") (pinfunction "VCC_1") (pintype "bidirectional"))
      (node (ref "JP4") (pin "12") (pinfunction "12_12") (pintype "passive"))
      (node (ref "LED1") (pin "A") (pinfunction "ANODE_A") (pintype "bidirectional"))
      (node (ref "R10") (pin "2") (pinfunction "2_2") (pintype "passive"))
      (node (ref "R11") (pin "2") (pinfunction "2_2") (pintype "passive"))
      (node (ref "R12") (pin "2") (pinfunction "2_2") (pintype "passive"))
      (node (ref "R6") (pin "2") (pinfunction "2_2") (pintype "passive"))
      (node (ref "R7") (pin "2") (pinfunction "2_2") (pintype "passive"))
      (node (ref "R8") (pin "2") (pinfunction "2_2") (pintype "passive"))
      (node (ref "U1") (pin "11") (pinfunction "~{RESET}_11") (pintype "bidirectional"))
      (node (ref "U1") (pin "12") (pinfunction "VCC_12") (pintype "bidirectional"))
      (node (ref "U1") (pin "20") (pinfunction "VCCIO_20") (pintype "bidirectional"))
      (node (ref "U2") (pin "1") (pinfunction "VDDIO_1") (pintype "bidirectional"))
      (node (ref "U2") (pin "14") (pinfunction "VDD_14") (pintype "bidirectional"))
      (node (ref "U3") (pin "1") (pinfunction "VDD_1") (pintype "bidirectional"))
      (node (ref "U4") (pin "5") (pinfunction "OUT_5") (pintype "bidirectional"))
      (node (ref "U5") (pin "1") (pinfunction "VDD_1") (pintype "bidirectional"))
      (node (ref "U5") (pin "12") (pinfunction "VDD_12") (pintype "bidirectional"))
      (node (ref "U5") (pin "35") (pinfunction "AVDD_35") (pintype "bidirectional"))
      (node (ref "U5") (pin "36") (pinfunction "AVDD_36") (pintype "bidirectional"))
      (node (ref "U6") (pin "35") (pinfunction "VLCD_35") (pintype "bidirectional"))
      (node (ref "U6") (pin "39") (pinfunction "VLCDIN_39") (pintype "power_in"))
      (node (ref "U6") (pin "52") (pinfunction "VDDIO_52") (pintype "power_in"))
      (node (ref "U6") (pin "61") (pinfunction "VDDIO_61") (pintype "power_in"))
      (node (ref "U6") (pin "8") (pinfunction "VDDIN_8") (pintype "power_in"))
      (node (ref "U7") (pin "5") (pinfunction "VCC_5") (pintype "bidirectional"))
    )
    (net (code "67") (name "unconnected-(J1-ID-Pad4)") (class "Default")
      (node (ref "J1") (pin "4") (pinfunction "ID_4") (pintype "bidirectional"))
    )
    (net (code "68") (name "unconnected-(J2-SWO-Pad6)") (class "Default")
      (node (ref "J2") (pin "6") (pinfunction "SWO_6") (pintype "bidirectional"))
    )
    (net (code "69") (name "unconnected-(J3-SWO-Pad6)") (class "Default")
      (node (ref "J3") (pin "6") (pinfunction "SWO_6") (pintype "bidirectional"))
    )
    (net (code "70") (name "unconnected-(J3-~{RESET}-Pad3)") (class "Default")
      (node (ref "J3") (pin "3") (pinfunction "~{RESET}_3") (pintype "bidirectional"))
    )
    (net (code "71") (name "unconnected-(JP4-Pad10)") (class "Default")
      (node (ref "JP4") (pin "10") (pinfunction "10_10") (pintype "passive"))
    )
    (net (code "72") (name "unconnected-(U1-3V3OUT-Pad10)") (class "Default")
      (node (ref "U1") (pin "10") (pinfunction "3V3OUT_10") (pintype "bidirectional"))
    )
    (net (code "73") (name "unconnected-(U1-CBUS0-Pad15)") (class "Default")
      (node (ref "U1") (pin "15") (pinfunction "CBUS0_15") (pintype "bidirectional"))
    )
    (net (code "74") (name "unconnected-(U1-CBUS1-Pad14)") (class "Default")
      (node (ref "U1") (pin "14") (pinfunction "CBUS1_14") (pintype "bidirectional"))
    )
    (net (code "75") (name "unconnected-(U1-CBUS2-Pad7)") (class "Default")
      (node (ref "U1") (pin "7") (pinfunction "CBUS2_7") (pintype "bidirectional"))
    )
    (net (code "76") (name "unconnected-(U1-CBUS3-Pad16)") (class "Default")
      (node (ref "U1") (pin "16") (pinfunction "CBUS3_16") (pintype "bidirectional"))
    )
    (net (code "77") (name "unconnected-(U1-~{CTS}-Pad6)") (class "Default")
      (node (ref "U1") (pin "6") (pinfunction "~{CTS}_6") (pintype "bidirectional"))
    )
    (net (code "78") (name "unconnected-(U1-~{DCD}-Pad5)") (class "Default")
      (node (ref "U1") (pin "5") (pinfunction "~{DCD}_5") (pintype "bidirectional"))
    )
    (net (code "79") (name "unconnected-(U1-~{DSR}-Pad4)") (class "Default")
      (node (ref "U1") (pin "4") (pinfunction "~{DSR}_4") (pintype "bidirectional"))
    )
    (net (code "80") (name "unconnected-(U1-~{RI}-Pad2)") (class "Default")
      (node (ref "U1") (pin "2") (pinfunction "~{RI}_2") (pintype "bidirectional"))
    )
    (net (code "81") (name "unconnected-(U5-DCC-Pad2)") (class "Default")
      (node (ref "U5") (pin "2") (pinfunction "DCC_2") (pintype "bidirectional"))
    )
    (net (code "82") (name "unconnected-(U5-P01{slash}AIN2-Pad5)") (class "Default")
      (node (ref "U5") (pin "5") (pinfunction "P01/AIN2_5") (pintype "bidirectional"))
    )
    (net (code "83") (name "unconnected-(U5-P02{slash}AIN3-Pad6)") (class "Default")
      (node (ref "U5") (pin "6") (pinfunction "P02/AIN3_6") (pintype "bidirectional"))
    )
    (net (code "84") (name "unconnected-(U5-P03{slash}AIN4-Pad7)") (class "Default")
      (node (ref "U5") (pin "7") (pinfunction "P03/AIN4_7") (pintype "bidirectional"))
    )
    (net (code "85") (name "unconnected-(U5-P04{slash}AIN5-Pad8)") (class "Default")
      (node (ref "U5") (pin "8") (pinfunction "P04/AIN5_8") (pintype "bidirectional"))
    )
    (net (code "86") (name "unconnected-(U5-P05{slash}AIN6-Pad9)") (class "Default")
      (node (ref "U5") (pin "9") (pinfunction "P05/AIN6_9") (pintype "bidirectional"))
    )
    (net (code "87") (name "unconnected-(U5-P06{slash}AIN7{slash}AREF1-Pad10)") (class "Default")
      (node (ref "U5") (pin "10") (pinfunction "P06/AIN7/AREF1_10") (pintype "bidirectional"))
    )
    (net (code "88") (name "unconnected-(U5-P07-Pad11)") (class "Default")
      (node (ref "U5") (pin "11") (pinfunction "P07_11") (pintype "bidirectional"))
    )
    (net (code "89") (name "unconnected-(U5-P08-Pad14)") (class "Default")
      (node (ref "U5") (pin "14") (pinfunction "P08_14") (pintype "bidirectional"))
    )
    (net (code "90") (name "unconnected-(U5-P09-Pad15)") (class "Default")
      (node (ref "U5") (pin "15") (pinfunction "P09_15") (pintype "bidirectional"))
    )
    (net (code "91") (name "unconnected-(U5-P10-Pad16)") (class "Default")
      (node (ref "U5") (pin "16") (pinfunction "P10_16") (pintype "bidirectional"))
    )
    (net (code "92") (name "unconnected-(U5-P16-Pad22)") (class "Default")
      (node (ref "U5") (pin "22") (pinfunction "P16_22") (pintype "bidirectional"))
    )
    (net (code "93") (name "unconnected-(U5-P17-Pad25)") (class "Default")
      (node (ref "U5") (pin "25") (pinfunction "P17_25") (pintype "bidirectional"))
    )
    (net (code "94") (name "unconnected-(U5-P18-Pad26)") (class "Default")
      (node (ref "U5") (pin "26") (pinfunction "P18_26") (pintype "bidirectional"))
    )
    (net (code "95") (name "unconnected-(U5-P19-Pad27)") (class "Default")
      (node (ref "U5") (pin "27") (pinfunction "P19_27") (pintype "bidirectional"))
    )
    (net (code "96") (name "unconnected-(U5-P20-Pad28)") (class "Default")
      (node (ref "U5") (pin "28") (pinfunction "P20_28") (pintype "bidirectional"))
    )
    (net (code "97") (name "unconnected-(U5-P21-Pad40)") (class "Default")
      (node (ref "U5") (pin "40") (pinfunction "P21_40") (pintype "bidirectional"))
    )
    (net (code "98") (name "unconnected-(U5-P22-Pad41)") (class "Default")
      (node (ref "U5") (pin "41") (pinfunction "P22_41") (pintype "bidirectional"))
    )
    (net (code "99") (name "unconnected-(U5-P23-Pad42)") (class "Default")
      (node (ref "U5") (pin "42") (pinfunction "P23_42") (pintype "bidirectional"))
    )
    (net (code "100") (name "unconnected-(U5-P24-Pad43)") (class "Default")
      (node (ref "U5") (pin "43") (pinfunction "P24_43") (pintype "bidirectional"))
    )
    (net (code "101") (name "unconnected-(U5-P25-Pad44)") (class "Default")
      (node (ref "U5") (pin "44") (pinfunction "P25_44") (pintype "bidirectional"))
    )
    (net (code "102") (name "unconnected-(U5-P26{slash}AIN0{slash}XL2-Pad45)") (class "Default")
      (node (ref "U5") (pin "45") (pinfunction "P26/AIN0/XL2_45") (pintype "bidirectional"))
    )
    (net (code "103") (name "unconnected-(U5-P27{slash}AIN1{slash}XL1-Pad46)") (class "Default")
      (node (ref "U5") (pin "46") (pinfunction "P27/AIN1/XL1_46") (pintype "bidirectional"))
    )
    (net (code "104") (name "unconnected-(U5-P28-Pad47)") (class "Default")
      (node (ref "U5") (pin "47") (pinfunction "P28_47") (pintype "bidirectional"))
    )
    (net (code "105") (name "unconnected-(U5-P29-Pad48)") (class "Default")
      (node (ref "U5") (pin "48") (pinfunction "P29_48") (pintype "bidirectional"))
    )
    (net (code "106") (name "unconnected-(U5-P30-Pad3)") (class "Default")
      (node (ref "U5") (pin "3") (pinfunction "P30_3") (pintype "bidirectional"))
    )
    (net (code "107") (name "unconnected-(U6-PA10-Pad30)") (class "Default")
      (node (ref "U6") (pin "30") (pinfunction "PA10_30") (pintype "bidirectional"))
    )
    (net (code "108") (name "unconnected-(U6-PA19-Pad50)") (class "Default")
      (node (ref "U6") (pin "50") (pinfunction "PA19_50") (pintype "bidirectional"))
    )
    (net (code "109") (name "unconnected-(U6-PB13-Pad54)") (class "Default")
      (node (ref "U6") (pin "54") (pinfunction "PB13_54") (pintype "bidirectional"))
    )
    (net (code "110") (name "unconnected-(U6-XIN32-Pad17)") (class "Default")
      (node (ref "U6") (pin "17") (pinfunction "XIN32_17") (pintype "bidirectional"))
    )
    (net (code "111") (name "unconnected-(U6-XOUT32-Pad18)") (class "Default")
      (node (ref "U6") (pin "18") (pinfunction "XOUT32_18") (pintype "bidirectional"))
    )
    (net (code "112") (name "~{FTDI_RTS}") (class "Default")
      (node (ref "TP11") (pin "TP") (pinfunction "TP_TP") (pintype "input"))
      (node (ref "U1") (pin "19") (pinfunction "~{RTS}_19") (pintype "bidirectional"))
      (node (ref "U6") (pin "26") (pinfunction "PA08_26") (pintype "bidirectional"))
    )
    (net (code "113") (name "~{LIGHT_INT}") (class "Default")
      (node (ref "R8") (pin "1") (pinfunction "1_1") (pintype "passive"))
      (node (ref "TP10") (pin "TP") (pinfunction "TP_TP") (pintype "input"))
      (node (ref "U3") (pin "4") (pinfunction "~{INT}_4") (pintype "bidirectional"))
      (node (ref "U6") (pin "51") (pinfunction "PA20_51") (pintype "bidirectional"))
    )
    (net (code "114") (name "~{NRF_RESET}") (class "Default")
      (node (ref "J3") (pin "2") (pinfunction "SWDIO_2") (pintype "bidirectional"))
      (node (ref "U5") (pin "23") (pinfunction "SWDIO/~{RESET}_23") (pintype "bidirectional"))
      (node (ref "U6") (pin "44") (pinfunction "PA17_44") (pintype "bidirectional"))
    )
    (net (code "115") (name "~{SAM4L_RESET}") (class "Default")
      (node (ref "J2") (pin "3") (pinfunction "~{RESET}_3") (pintype "bidirectional"))
      (node (ref "JP4") (pin "11") (pinfunction "11_11") (pintype "passive"))
      (node (ref "S1") (pin "1") (pinfunction "P$1_1") (pintype "passive"))
      (node (ref "U1") (pin "18") (pinfunction "~{DTR}_18") (pintype "bidirectional"))
      (node (ref "U6") (pin "4") (pinfunction "~{RESET}_4") (pintype "bidirectional"))
    )
  )
)
